# MGT.net
KiCad netlist of a schematic drawn in Altium Designer
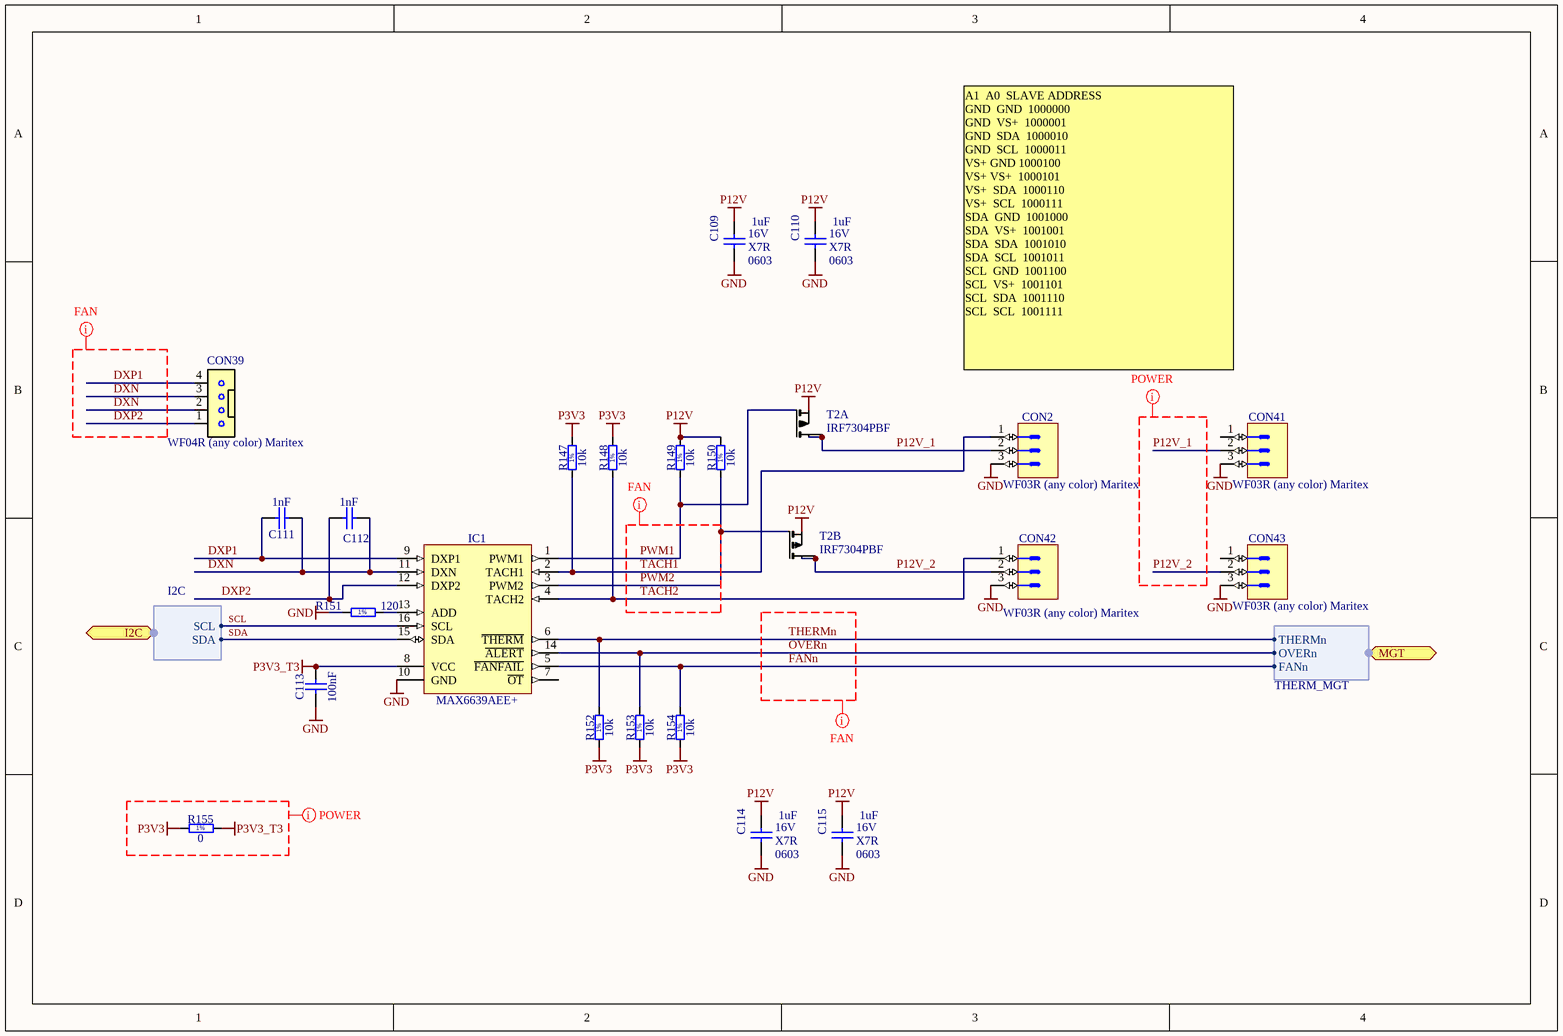
[diagram p0: MGT.SchDoc]

(export (version "E")
  (design (tool "Eeschema 10.0.6"))
  (components
    (comp (ref "C109")
      (value "1uF")
      (footprint "CAPC1608X87N")
      (description "Non-polarised capacitor")
      (fields
        (field (name "PART NUMBER") "CC0603_1UF_16V_10%_X7R")
        (field (name "VOLTAGE") "16V")
        (field (name "TC") "X7R")
        (field (name "TOLERANCE") "±10%")
        (field (name "CASE") "0603")
        (field (name "AUTHOR") "CERN DEM JLC")
      )
      (libsource (lib "Capacitors") (part "Capacitor - non polarized"))
    )
    (comp (ref "C110")
      (value "1uF")
      (footprint "CAPC1608X87N")
      (description "Non-polarised capacitor")
      (fields
        (field (name "PART NUMBER") "CC0603_1UF_16V_10%_X7R")
        (field (name "VOLTAGE") "16V")
        (field (name "TC") "X7R")
        (field (name "TOLERANCE") "±10%")
        (field (name "CASE") "0603")
        (field (name "AUTHOR") "CERN DEM JLC")
      )
      (libsource (lib "Capacitors") (part "Capacitor - non polarized"))
    )
    (comp (ref "C111")
      (value "1nF")
      (footprint "CAPC1608X87N")
      (description "Non-polarised capacitor")
      (fields
        (field (name "PART NUMBER") "CC0603_1NF_50V_10%_X7R")
        (field (name "VOLTAGE") "50V")
        (field (name "AUTHOR") "CERN DEM JLC")
      )
      (libsource (lib "Capacitors") (part "Capacitor - non polarized"))
    )
    (comp (ref "C112")
      (value "1nF")
      (footprint "CAPC1608X87N")
      (description "Non-polarised capacitor")
      (fields
        (field (name "PART NUMBER") "CC0603_1NF_50V_10%_X7R")
        (field (name "VOLTAGE") "50V")
        (field (name "AUTHOR") "CERN DEM JLC")
      )
      (libsource (lib "Capacitors") (part "Capacitor - non polarized"))
    )
    (comp (ref "C113")
      (value "100nF")
      (footprint "CAPC0603X33N")
      (description "Non-polarised capacitor")
      (fields
        (field (name "PART NUMBER") "CC0201_100NF_6.3V_10%_X5R")
        (field (name "VOLTAGE") "6.3V")
        (field (name "AUTHOR") "CERN DEM JLC")
      )
      (libsource (lib "Capacitors") (part "Capacitor - non polarized"))
    )
    (comp (ref "C114")
      (value "1uF")
      (footprint "CAPC1608X87N")
      (description "Non-polarised capacitor")
      (fields
        (field (name "PART NUMBER") "CC0603_1UF_16V_10%_X7R")
        (field (name "VOLTAGE") "16V")
        (field (name "TC") "X7R")
        (field (name "TOLERANCE") "±10%")
        (field (name "CASE") "0603")
        (field (name "AUTHOR") "CERN DEM JLC")
      )
      (libsource (lib "Capacitors") (part "Capacitor - non polarized"))
    )
    (comp (ref "C115")
      (value "1uF")
      (footprint "CAPC1608X87N")
      (description "Non-polarised capacitor")
      (fields
        (field (name "PART NUMBER") "CC0603_1UF_16V_10%_X7R")
        (field (name "VOLTAGE") "16V")
        (field (name "TC") "X7R")
        (field (name "TOLERANCE") "±10%")
        (field (name "CASE") "0603")
        (field (name "AUTHOR") "CERN DEM JLC")
      )
      (libsource (lib "Capacitors") (part "Capacitor - non polarized"))
    )
    (comp (ref "CON2")
      (value "WF03R (any color) Maritex")
      (footprint "MOLEX_22-05-7038")
      (description "Connector 3 Male")
      (fields
        (field (name "PART NUMBER") "MOLEX_22-05-7038")
        (field (name "MANUFACTURER") "MOLEX")
        (field (name "AUTHOR") "CERN DEM JLC")
      )
      (libsource (lib "Connectors") (part "Connector 3 Male"))
    )
    (comp (ref "CON39")
      (value "WF04R (any color) Maritex")
      (footprint "CON_0022057048")
      (description "2.54mm crimped terminal header")
      (libsource (lib "LIBRARY_SCH") (part "CON_4_2.54_RA_key"))
    )
    (comp (ref "CON41")
      (value "WF03R (any color) Maritex")
      (footprint "MOLEX_22-05-7038")
      (description "Connector 3 Male")
      (fields
        (field (name "PART NUMBER") "MOLEX_22-05-7038")
        (field (name "MANUFACTURER") "MOLEX")
        (field (name "AUTHOR") "CERN DEM JLC")
      )
      (libsource (lib "Connectors") (part "Connector 3 Male"))
    )
    (comp (ref "CON42")
      (value "WF03R (any color) Maritex")
      (footprint "MOLEX_22-05-7038")
      (description "Connector 3 Male")
      (fields
        (field (name "PART NUMBER") "MOLEX_22-05-7038")
        (field (name "MANUFACTURER") "MOLEX")
        (field (name "AUTHOR") "CERN DEM JLC")
      )
      (libsource (lib "Connectors") (part "Connector 3 Male"))
    )
    (comp (ref "CON43")
      (value "WF03R (any color) Maritex")
      (footprint "MOLEX_22-05-7038")
      (description "Connector 3 Male")
      (fields
        (field (name "PART NUMBER") "MOLEX_22-05-7038")
        (field (name "MANUFACTURER") "MOLEX")
        (field (name "AUTHOR") "CERN DEM JLC")
      )
      (libsource (lib "Connectors") (part "Connector 3 Male"))
    )
    (comp (ref "IC1")
      (value "MAX6639AEE+")
      (footprint "SOP63P600X175-16N")
      (description "2-Channel Temperature Monitor with Dual, Automatic, PWM Fan-Speed Controller")
      (fields (field (name "MANUFACTURER") "MAXIM") (field (name "AUTHOR") "CERN DEM JLC"))
      (libsource (lib "ICs And Semiconductors") (part "MAX6639AEE+"))
    )
    (comp (ref "R147")
      (value "10k")
      (footprint "RESC1005X40N")
      (description "Resistor - 1%")
      (fields
        (field (name "PART NUMBER") "R0402_10K_1%_0.0625W_100PPM")
        (field (name "POWER") "0.0625W")
        (field (name "AUTHOR") "CERN DEM JLC")
      )
      (libsource (lib "Resistors") (part "Resistor - 1%"))
    )
    (comp (ref "R148")
      (value "10k")
      (footprint "RESC1005X40N")
      (description "Resistor - 1%")
      (fields
        (field (name "PART NUMBER") "R0402_10K_1%_0.0625W_100PPM")
        (field (name "POWER") "0.0625W")
        (field (name "AUTHOR") "CERN DEM JLC")
      )
      (libsource (lib "Resistors") (part "Resistor - 1%"))
    )
    (comp (ref "R149")
      (value "10k")
      (footprint "RESC1005X40N")
      (description "Resistor - 1%")
      (fields
        (field (name "PART NUMBER") "R0402_10K_1%_0.0625W_100PPM")
        (field (name "POWER") "0.0625W")
        (field (name "AUTHOR") "CERN DEM JLC")
      )
      (libsource (lib "Resistors") (part "Resistor - 1%"))
    )
    (comp (ref "R150")
      (value "10k")
      (footprint "RESC1005X40N")
      (description "Resistor - 1%")
      (fields
        (field (name "PART NUMBER") "R0402_10K_1%_0.0625W_100PPM")
        (field (name "POWER") "0.0625W")
        (field (name "AUTHOR") "CERN DEM JLC")
      )
      (libsource (lib "Resistors") (part "Resistor - 1%"))
    )
    (comp (ref "R151")
      (value "120")
      (footprint "RESC1005X40N")
      (description "Resistor - 1%")
      (fields
        (field (name "PART NUMBER") "R0402_120R_1%_0.0625W_100PPM")
        (field (name "POWER") "0.0625W")
        (field (name "AUTHOR") "CERN DEM JLC")
      )
      (libsource (lib "Resistors") (part "Resistor - 1%"))
    )
    (comp (ref "R152")
      (value "10k")
      (footprint "RESC1005X40N")
      (description "Resistor - 1%")
      (fields
        (field (name "PART NUMBER") "R0402_10K_1%_0.0625W_100PPM")
        (field (name "POWER") "0.0625W")
        (field (name "AUTHOR") "CERN DEM JLC")
      )
      (libsource (lib "Resistors") (part "Resistor - 1%"))
    )
    (comp (ref "R153")
      (value "10k")
      (footprint "RESC1005X40N")
      (description "Resistor - 1%")
      (fields
        (field (name "PART NUMBER") "R0402_10K_1%_0.0625W_100PPM")
        (field (name "POWER") "0.0625W")
        (field (name "AUTHOR") "CERN DEM JLC")
      )
      (libsource (lib "Resistors") (part "Resistor - 1%"))
    )
    (comp (ref "R154")
      (value "10k")
      (footprint "RESC1005X40N")
      (description "Resistor - 1%")
      (fields
        (field (name "PART NUMBER") "R0402_10K_1%_0.0625W_100PPM")
        (field (name "POWER") "0.0625W")
        (field (name "AUTHOR") "CERN DEM JLC")
      )
      (libsource (lib "Resistors") (part "Resistor - 1%"))
    )
    (comp (ref "R155")
      (value "0")
      (footprint "RESC1608X55N")
      (description "Resistor - 1%")
      (fields
        (field (name "PART NUMBER") "R0603_0R_JUMPER")
        (field (name "MANUFACTURER") "GENERIC")
        (field (name "AUTHOR") "CERN DEM JLC")
      )
      (libsource (lib "Resistors") (part "Resistor - 1%"))
    )
    (comp (ref "T2")
      (value "IRF7304PBF")
      (footprint "so-8")
      (description "dual PMOS   20V 4,3A 2,0W 0,09R")
      (libsource (lib "LIBRARY_SCH") (part "Q_IRF7304"))
    )
  )
  (nets
    (net (code "3") (name "/DXN") (class "Default")
      (node (ref "C111") (pin "1") (pinfunction "1_1") (pintype "passive"))
      (node (ref "C112") (pin "1") (pinfunction "1_1") (pintype "passive"))
      (node (ref "CON39") (pin "2") (pinfunction "2_2") (pintype "bidirectional"))
      (node (ref "CON39") (pin "3") (pinfunction "3_3") (pintype "bidirectional"))
      (node (ref "IC1") (pin "11") (pinfunction "DXN_11") (pintype "input"))
    )
    (net (code "4") (name "/DXP1") (class "Default")
      (node (ref "C111") (pin "2") (pinfunction "2_2") (pintype "passive"))
      (node (ref "CON39") (pin "4") (pinfunction "4_4") (pintype "bidirectional"))
      (node (ref "IC1") (pin "9") (pinfunction "DXP1_9") (pintype "input"))
    )
    (net (code "5") (name "/DXP2") (class "Default")
      (node (ref "C112") (pin "2") (pinfunction "2_2") (pintype "passive"))
      (node (ref "CON39") (pin "1") (pinfunction "1_1") (pintype "bidirectional"))
      (node (ref "IC1") (pin "12") (pinfunction "DXP2_12") (pintype "input"))
    )
    (net (code "6") (name "/FANn") (class "Default")
      (node (ref "IC1") (pin "5") (pinfunction "~{FANFAIL}_5") (pintype "output"))
      (node (ref "R154") (pin "2") (pinfunction "2_2") (pintype "passive"))
    )
    (net (code "7") (name "/OVERn") (class "Default")
      (node (ref "IC1") (pin "14") (pinfunction "~{ALERT}_14") (pintype "output"))
      (node (ref "R153") (pin "2") (pinfunction "2_2") (pintype "passive"))
    )
    (net (code "8") (name "/P12V_1") (class "Default")
      (node (ref "CON2") (pin "2") (pinfunction "2_2") (pintype "bidirectional"))
      (node (ref "CON41") (pin "2") (pinfunction "2_2") (pintype "bidirectional"))
      (node (ref "T2") (pin "7") (pinfunction "D1_7") (pintype "passive"))
      (node (ref "T2") (pin "8") (pinfunction "D1_8") (pintype "passive"))
    )
    (net (code "9") (name "/P12V_2") (class "Default")
      (node (ref "CON42") (pin "2") (pinfunction "2_2") (pintype "bidirectional"))
      (node (ref "CON43") (pin "2") (pinfunction "2_2") (pintype "bidirectional"))
      (node (ref "T2") (pin "5") (pinfunction "D2_5") (pintype "passive"))
      (node (ref "T2") (pin "6") (pinfunction "D2_6") (pintype "passive"))
    )
    (net (code "10") (name "/PWM1") (class "Default")
      (node (ref "IC1") (pin "1") (pinfunction "PWM1_1") (pintype "output"))
      (node (ref "R149") (pin "1") (pinfunction "1_1") (pintype "passive"))
      (node (ref "T2") (pin "2") (pinfunction "G1_2") (pintype "input"))
    )
    (net (code "11") (name "/PWM2") (class "Default")
      (node (ref "IC1") (pin "3") (pinfunction "PWM2_3") (pintype "output"))
      (node (ref "R150") (pin "1") (pinfunction "1_1") (pintype "passive"))
      (node (ref "T2") (pin "4") (pinfunction "G2_4") (pintype "input"))
    )
    (net (code "12") (name "/SCL") (class "Default")
      (node (ref "IC1") (pin "16") (pinfunction "SCL_16") (pintype "input"))
    )
    (net (code "13") (name "/SDA") (class "Default")
      (node (ref "IC1") (pin "15") (pinfunction "SDA_15") (pintype "bidirectional"))
    )
    (net (code "14") (name "/TACH1") (class "Default")
      (node (ref "CON2") (pin "1") (pinfunction "1_1") (pintype "bidirectional"))
      (node (ref "IC1") (pin "2") (pinfunction "TACH1_2") (pintype "input"))
      (node (ref "R147") (pin "1") (pinfunction "1_1") (pintype "passive"))
    )
    (net (code "15") (name "/TACH2") (class "Default")
      (node (ref "CON42") (pin "1") (pinfunction "1_1") (pintype "bidirectional"))
      (node (ref "IC1") (pin "4") (pinfunction "TACH2_4") (pintype "input"))
      (node (ref "R148") (pin "1") (pinfunction "1_1") (pintype "passive"))
    )
    (net (code "16") (name "/THERMn") (class "Default")
      (node (ref "IC1") (pin "6") (pinfunction "~{THERM}_6") (pintype "output"))
      (node (ref "R152") (pin "2") (pinfunction "2_2") (pintype "passive"))
    )
    (net (code "19") (name "GND") (class "Default")
      (node (ref "C109") (pin "1") (pinfunction "1_1") (pintype "passive"))
      (node (ref "C110") (pin "1") (pinfunction "1_1") (pintype "passive"))
      (node (ref "C113") (pin "1") (pinfunction "1_1") (pintype "passive"))
      (node (ref "C114") (pin "1") (pinfunction "1_1") (pintype "passive"))
      (node (ref "C115") (pin "1") (pinfunction "1_1") (pintype "passive"))
      (node (ref "CON2") (pin "3") (pinfunction "3_3") (pintype "bidirectional"))
      (node (ref "CON41") (pin "3") (pinfunction "3_3") (pintype "bidirectional"))
      (node (ref "CON42") (pin "3") (pinfunction "3_3") (pintype "bidirectional"))
      (node (ref "CON43") (pin "3") (pinfunction "3_3") (pintype "bidirectional"))
      (node (ref "IC1") (pin "10") (pinfunction "GND_10") (pintype "power_in"))
      (node (ref "R151") (pin "1") (pinfunction "1_1") (pintype "passive"))
    )
    (net (code "20") (name "Net-(IC1-ADD)") (class "Default")
      (node (ref "IC1") (pin "13") (pinfunction "ADD_13") (pintype "input"))
      (node (ref "R151") (pin "2") (pinfunction "2_2") (pintype "passive"))
    )
    (net (code "21") (name "P3V3") (class "Default")
      (node (ref "R147") (pin "2") (pinfunction "2_2") (pintype "passive"))
      (node (ref "R148") (pin "2") (pinfunction "2_2") (pintype "passive"))
      (node (ref "R152") (pin "1") (pinfunction "1_1") (pintype "passive"))
      (node (ref "R153") (pin "1") (pinfunction "1_1") (pintype "passive"))
      (node (ref "R154") (pin "1") (pinfunction "1_1") (pintype "passive"))
      (node (ref "R155") (pin "1") (pinfunction "1_1") (pintype "passive"))
    )
    (net (code "22") (name "P3V3_T3") (class "Default")
      (node (ref "C113") (pin "2") (pinfunction "2_2") (pintype "passive"))
      (node (ref "IC1") (pin "8") (pinfunction "VCC_8") (pintype "power_in"))
      (node (ref "R155") (pin "2") (pinfunction "2_2") (pintype "passive"))
    )
    (net (code "23") (name "P12V") (class "Default")
      (node (ref "C109") (pin "2") (pinfunction "2_2") (pintype "passive"))
      (node (ref "C110") (pin "2") (pinfunction "2_2") (pintype "passive"))
      (node (ref "C114") (pin "2") (pinfunction "2_2") (pintype "passive"))
      (node (ref "C115") (pin "2") (pinfunction "2_2") (pintype "passive"))
      (node (ref "R149") (pin "2") (pinfunction "2_2") (pintype "passive"))
      (node (ref "R150") (pin "2") (pinfunction "2_2") (pintype "passive"))
      (node (ref "T2") (pin "1") (pinfunction "S1_1") (pintype "passive"))
      (node (ref "T2") (pin "3") (pinfunction "S2_3") (pintype "passive"))
    )
    (net (code "24") (name "unconnected-(CON41-Pad1)") (class "Default")
      (node (ref "CON41") (pin "1") (pinfunction "1_1") (pintype "bidirectional"))
    )
    (net (code "25") (name "unconnected-(CON43-Pad1)") (class "Default")
      (node (ref "CON43") (pin "1") (pinfunction "1_1") (pintype "bidirectional"))
    )
    (net (code "26") (name "unconnected-(IC1-~{OT}-Pad7)") (class "Default")
      (node (ref "IC1") (pin "7") (pinfunction "~{OT}_7") (pintype "output"))
    )
  )
)
